# 4_analog_circuits.net
KiCad netlist of a schematic drawn in Altium Designer
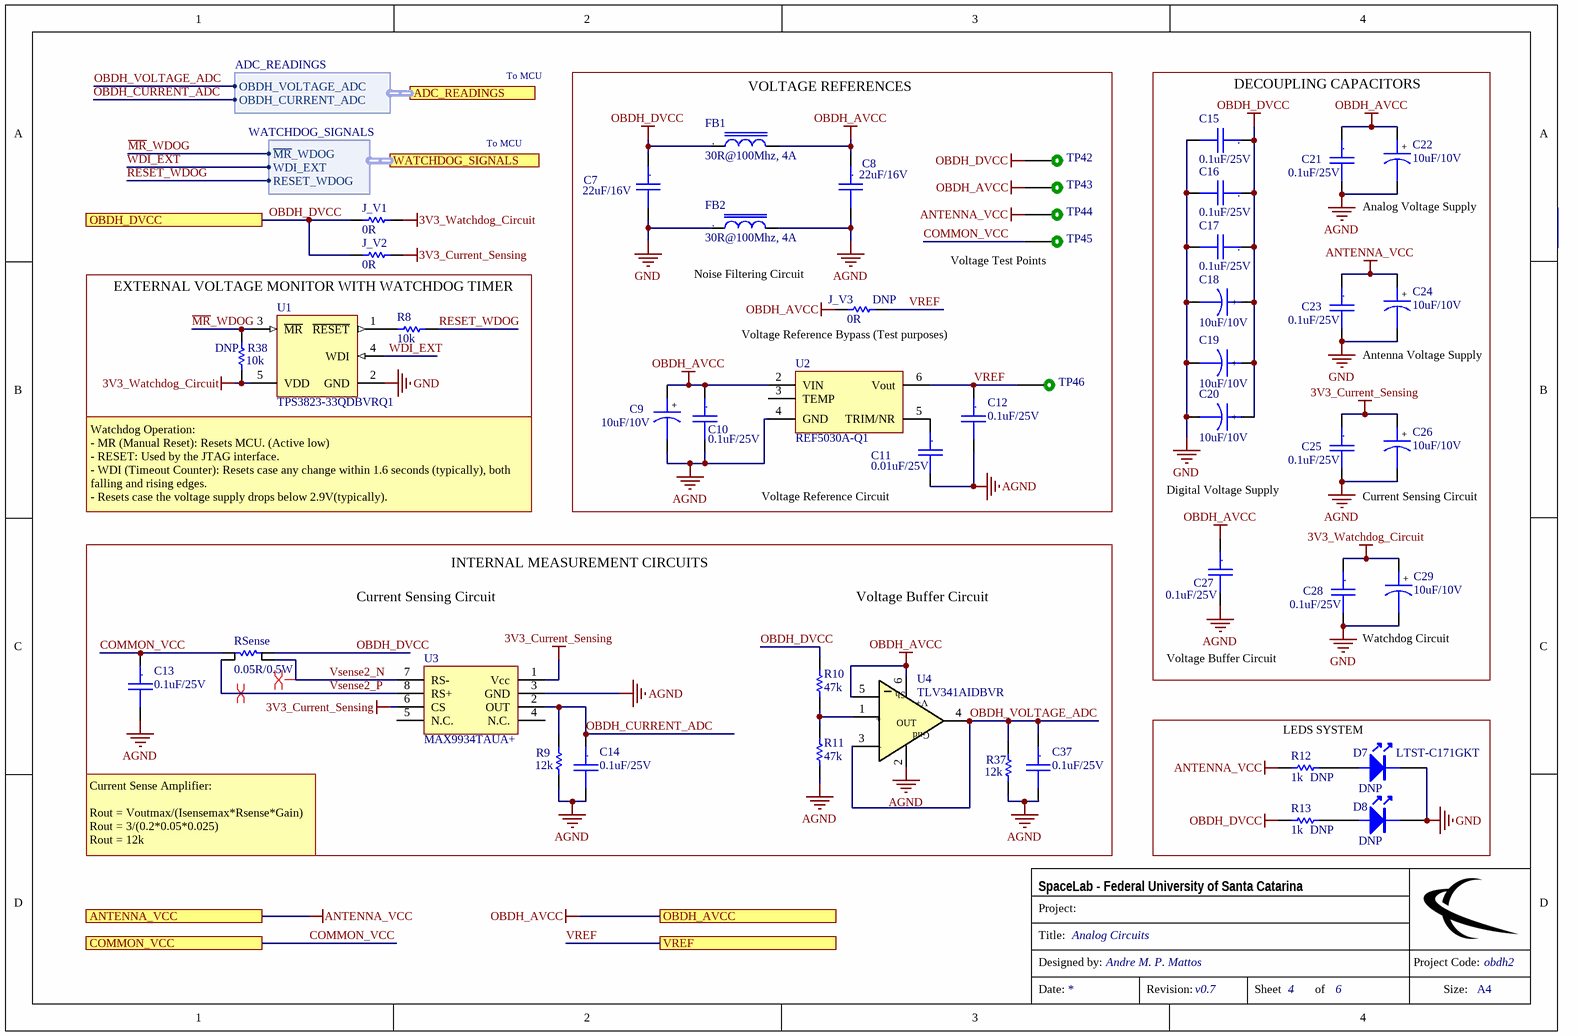
[diagram p0: 4_analog_circuits.schdoc]

(export (version "E")
  (design (tool "Eeschema 10.0.6"))
  (components
    (comp (ref "C7")
      (value "22uF/16V")
      (footprint "CC1210")
      (description "CAP CER 22uF 16V 10% X7R 1210")
      (fields (field (name "PARTNUMBER") "C3225X7R1C226K250AC"))
      (libsource (lib "OBDH_Eng_Model_2_ALT") (part "Cap_Cer_X7R_0.01uF_16V_1210"))
    )
    (comp (ref "C8")
      (value "22uF/16V")
      (footprint "CC1210")
      (description "CAP CER 22uF 16V 10% X7R 1210")
      (fields (field (name "PARTNUMBER") "C3225X7R1C226K250AC"))
      (libsource (lib "OBDH_Eng_Model_2_ALT") (part "Cap_Cer_X7R_0.01uF_16V_1210"))
    )
    (comp (ref "C9")
      (value "10uF/10V")
      (footprint "CC0805_Tantalum")
      (description "CAP Tantalum 10uF 6.3V 10% 0805")
      (fields (field (name "PARTNUMBER") "TPSR106K006R1000"))
      (libsource (lib "") (part "Cap_Tant_SMD_10uF_6V3_0805_1"))
    )
    (comp (ref "C10")
      (value "0.1uF/25V")
      (footprint "CC0805")
      (description "CAP CER 0.1UF 25V 10% X7R 0805")
      (fields (field (name "PARTNUMBER") "CC0805KRX7R8BB104"))
      (libsource (lib "OBDH_Eng_Model_2_ALT") (part "Cap_Cer_X7R_0.1uF_25V_0805"))
    )
    (comp (ref "C11")
      (value "0.01uF/25V")
      (footprint "CC0805")
      (description "CAP CER 0.01uF 25V 10% X7R 0805")
      (fields (field (name "PARTNUMBER") "CL21B103KAANNNC"))
      (libsource (lib "OBDH_Eng_Model_2_ALT") (part "Cap_Cer_X7R_0.01uF_50V_0805"))
    )
    (comp (ref "C12")
      (value "0.1uF/25V")
      (footprint "CC0805")
      (description "CAP CER 0.1UF 25V 10% X7R 0805")
      (fields (field (name "PARTNUMBER") "CC0805KRX7R8BB104"))
      (libsource (lib "OBDH_Eng_Model_2_ALT") (part "Cap_Cer_X7R_0.1uF_25V_0805"))
    )
    (comp (ref "C13")
      (value "0.1uF/25V")
      (footprint "CC0805")
      (description "CAP CER 0.1UF 25V 10% X7R 0805")
      (fields (field (name "PARTNUMBER") "CC0805KRX7R8BB104"))
      (libsource (lib "OBDH_Eng_Model_2_ALT") (part "Cap_Cer_X7R_0.1uF_25V_0805"))
    )
    (comp (ref "C14")
      (value "0.1uF/25V")
      (footprint "CC0805")
      (description "CAP CER 0.1UF 25V 10% X7R 0805")
      (fields (field (name "PARTNUMBER") "CC0805KRX7R8BB104"))
      (libsource (lib "OBDH_Eng_Model_2_ALT") (part "Cap_Cer_X7R_0.1uF_25V_0805"))
    )
    (comp (ref "C15")
      (value "0.1uF/25V")
      (footprint "CC0805")
      (description "CAP CER 0.1UF 25V 10% X7R 0805")
      (fields (field (name "PARTNUMBER") "CC0805KRX7R8BB104"))
      (libsource (lib "OBDH_Eng_Model_2_ALT") (part "Cap_Cer_X7R_0.1uF_25V_0805"))
    )
    (comp (ref "C16")
      (value "0.1uF/25V")
      (footprint "CC0805")
      (description "CAP CER 0.1UF 25V 10% X7R 0805")
      (fields (field (name "PARTNUMBER") "CC0805KRX7R8BB104"))
      (libsource (lib "OBDH_Eng_Model_2_ALT") (part "Cap_Cer_X7R_0.1uF_25V_0805"))
    )
    (comp (ref "C17")
      (value "0.1uF/25V")
      (footprint "CC0805")
      (description "CAP CER 0.1UF 25V 10% X7R 0805")
      (fields (field (name "PARTNUMBER") "CC0805KRX7R8BB104"))
      (libsource (lib "OBDH_Eng_Model_2_ALT") (part "Cap_Cer_X7R_0.1uF_25V_0805"))
    )
    (comp (ref "C18")
      (value "10uF/10V")
      (footprint "CC0805_Tantalum")
      (description "CAP Tantalum 10uF 6.3V 10% 0805")
      (fields (field (name "PARTNUMBER") "TPSR106K006R1000"))
      (libsource (lib "OBDH_Eng_Model_2_ALT") (part "Cap_Tant_SMD_10uF_6V3_0805"))
    )
    (comp (ref "C19")
      (value "10uF/10V")
      (footprint "CC0805_Tantalum")
      (description "CAP Tantalum 10uF 6.3V 10% 0805")
      (fields (field (name "PARTNUMBER") "TPSR106K006R1000"))
      (libsource (lib "OBDH_Eng_Model_2_ALT") (part "Cap_Tant_SMD_10uF_6V3_0805"))
    )
    (comp (ref "C20")
      (value "10uF/10V")
      (footprint "CC0805_Tantalum")
      (description "CAP Tantalum 10uF 6.3V 10% 0805")
      (fields (field (name "PARTNUMBER") "TPSR106K006R1000"))
      (libsource (lib "OBDH_Eng_Model_2_ALT") (part "Cap_Tant_SMD_10uF_6V3_0805"))
    )
    (comp (ref "C21")
      (value "0.1uF/25V")
      (footprint "CC0805")
      (description "CAP CER 0.1UF 25V 10% X7R 0805")
      (fields (field (name "PARTNUMBER") "CC0805KRX7R8BB104"))
      (libsource (lib "OBDH_Eng_Model_2_ALT") (part "Cap_Cer_X7R_0.1uF_25V_0805"))
    )
    (comp (ref "C22")
      (value "10uF/10V")
      (footprint "CC0805_Tantalum")
      (description "CAP Tantalum 10uF 10V 20% 0805")
      (fields (field (name "PARTNUMBER") "TPSP106M010R2000"))
      (libsource (lib "OBDH_Eng_Model_2_ALT") (part "Cap_Tant_SMD_10uF_10V_0805"))
    )
    (comp (ref "C23")
      (value "0.1uF/25V")
      (footprint "CC0805")
      (description "CAP CER 0.1UF 25V 10% X7R 0805")
      (fields (field (name "PARTNUMBER") "CC0805KRX7R8BB104"))
      (libsource (lib "OBDH_Eng_Model_2_ALT") (part "Cap_Cer_X7R_0.1uF_25V_0805"))
    )
    (comp (ref "C24")
      (value "10uF/10V")
      (footprint "CC0805_Tantalum")
      (description "CAP Tantalum 10uF 10V 20% 0805")
      (fields (field (name "PARTNUMBER") "TPSP106M010R2000"))
      (libsource (lib "OBDH_Eng_Model_2_ALT") (part "Cap_Tant_SMD_10uF_10V_0805"))
    )
    (comp (ref "C25")
      (value "0.1uF/25V")
      (footprint "CC0805")
      (description "CAP CER 0.1UF 25V 10% X7R 0805")
      (fields (field (name "PARTNUMBER") "CC0805KRX7R8BB104"))
      (libsource (lib "OBDH_Eng_Model_2_ALT") (part "Cap_Cer_X7R_0.1uF_25V_0805"))
    )
    (comp (ref "C26")
      (value "10uF/10V")
      (footprint "CC0805_Tantalum")
      (description "CAP Tantalum 10uF 10V 20% 0805")
      (fields (field (name "PARTNUMBER") "TPSP106M010R2000"))
      (libsource (lib "OBDH_Eng_Model_2_ALT") (part "Cap_Tant_SMD_10uF_10V_0805"))
    )
    (comp (ref "C27")
      (value "0.1uF/25V")
      (footprint "CC0805")
      (description "CAP CER 0.1UF 25V 10% X7R 0805")
      (fields (field (name "PARTNUMBER") "CC0805KRX7R8BB104"))
      (libsource (lib "FloripaSatSchlib") (part "Cap_Cer_X7R_0.1uF_25V_0805"))
    )
    (comp (ref "C28")
      (value "0.1uF/25V")
      (footprint "CC0805")
      (description "CAP CER 0.1UF 25V 10% X7R 0805")
      (fields (field (name "PARTNUMBER") "CC0805KRX7R8BB104"))
      (libsource (lib "OBDH_Eng_Model_2_ALT") (part "Cap_Cer_X7R_0.1uF_25V_0805"))
    )
    (comp (ref "C29")
      (value "10uF/10V")
      (footprint "CC0805_Tantalum")
      (description "CAP Tantalum 10uF 10V 20% 0805")
      (fields (field (name "PARTNUMBER") "TPSP106M010R2000"))
      (libsource (lib "OBDH_Eng_Model_2_ALT") (part "Cap_Tant_SMD_10uF_10V_0805"))
    )
    (comp (ref "C37")
      (value "0.1uF/25V")
      (footprint "CC0805")
      (description "CAP CER 0.1UF 25V 10% X7R 0805")
      (fields (field (name "PARTNUMBER") "CC0805KRX7R8BB104"))
      (libsource (lib "OBDH_Eng_Model_2_ALT") (part "Cap_Cer_X7R_0.1uF_25V_0805"))
    )
    (comp (ref "D7")
      (value "DNP")
      (footprint "0805-LED")
      (description "SMD Green LED")
      (fields (field (name "PARTNUMBER") "LTST-C171GKT"))
      (libsource (lib "OBDH_Eng_Model_2_ALT") (part "LED/G_0805"))
    )
    (comp (ref "D8")
      (value "DNP")
      (footprint "0805-LED")
      (description "SMD Green LED")
      (fields (field (name "PARTNUMBER") "LTST-C171GKT"))
      (libsource (lib "OBDH_Eng_Model_2_ALT") (part "LED/G_0805"))
    )
    (comp (ref "FB1")
      (value "30R@100Mhz, 4A")
      (footprint "IND0805")
      (description "Ferrite Bead 30 OHM 4A 100MHz")
      (fields (field (name "PARTNUMBER") "BLM21PG300SN1D"))
      (libsource (lib "schematics_library_legacy") (part "FB_30R_4A_100MHz_0805"))
    )
    (comp (ref "FB2")
      (value "30R@100Mhz, 4A")
      (footprint "IND0805")
      (description "Ferrite Bead 30 OHM 4A 100MHz")
      (fields (field (name "PARTNUMBER") "BLM21PG300SN1D"))
      (libsource (lib "schematics_library_legacy") (part "FB_30R_4A_100MHz_0805"))
    )
    (comp (ref "J_V1")
      (value "0R")
      (footprint "0805")
      (description "RES 0R OHM 1/8W JUMPER 0805")
      (fields (field (name "PARTNUMBER") "CRCW08050000Z0EA"))
      (libsource (lib "schematics_library_legacy") (part "R0R_JUMPER_1/8W_0805"))
    )
    (comp (ref "J_V2")
      (value "0R")
      (footprint "0805")
      (description "RES 0R OHM 1/8W JUMPER 0805")
      (fields (field (name "PARTNUMBER") "CRCW08050000Z0EA"))
      (libsource (lib "schematics_library_legacy") (part "R0R_JUMPER_1/8W_0805"))
    )
    (comp (ref "J_V3")
      (value "0R")
      (footprint "0805")
      (description "RES 0R OHM 1/8W JUMPER 0805")
      (fields (field (name "PARTNUMBER") "CRCW08050000Z0EA"))
      (libsource (lib "schematics_library_legacy") (part "R0R_JUMPER_1/8W_0805"))
    )
    (comp (ref "R8")
      (value "10k")
      (footprint "0805")
      (description "RES 10K OHM 1/8W 1%  0805")
      (fields (field (name "PARTNUMBER") "CRCW080510K0FKEA"))
      (libsource (lib "OBDH_Eng_Model_2_ALT") (part "R10k_1%_1/8W_0805"))
    )
    (comp (ref "R9")
      (value "12k")
      (footprint "0805")
      (description "RES 12K OHM 1/8W 1%  0805")
      (fields (field (name "PARTNUMBER") "RC0805FR-0712KL"))
      (libsource (lib "schematics_library_legacy") (part "R12k_1%_1/8W_0805"))
    )
    (comp (ref "R10")
      (value "47k")
      (footprint "0805")
      (description "RES 47k OHM 1/8W 1% 0805")
      (fields (field (name "PARTNUMBER") "RC0805FR-0747KL"))
      (libsource (lib "schematics_library_legacy") (part "R47k_1%_1/8W_0805"))
    )
    (comp (ref "R11")
      (value "47k")
      (footprint "0805")
      (description "RES 47k OHM 1/8W 1% 0805")
      (fields (field (name "PARTNUMBER") "RC0805FR-0747KL"))
      (libsource (lib "schematics_library_legacy") (part "R47k_1%_1/8W_0805"))
    )
    (comp (ref "R12")
      (value "1k")
      (footprint "0805")
      (description "RES 1.0K OHM 1/8W 1% 0805")
      (fields (field (name "PARTNUMBER") "RC0805FR-071KL"))
      (libsource (lib "OBDH_Eng_Model_2_ALT") (part "R1.0k_1%_1/8W_0805"))
    )
    (comp (ref "R13")
      (value "1k")
      (footprint "0805")
      (description "RES 1.0K OHM 1/8W 1% 0805")
      (fields (field (name "PARTNUMBER") "RC0805FR-071KL"))
      (libsource (lib "OBDH_Eng_Model_2_ALT") (part "R1.0k_1%_1/8W_0805"))
    )
    (comp (ref "R37")
      (value "12k")
      (footprint "0805")
      (description "RES 12K OHM 1/8W 1%  0805")
      (fields (field (name "PARTNUMBER") "RC0805FR-0712KL"))
      (libsource (lib "schematics_library_legacy") (part "R12k_1%_1/8W_0805"))
    )
    (comp (ref "R38")
      (value "10k")
      (footprint "0805")
      (description "RES 10K OHM 1/8W 1%  0805")
      (fields (field (name "PARTNUMBER") "CRCW080510K0FKEA"))
      (libsource (lib "OBDH_Eng_Model_2_ALT") (part "R10k_1%_1/8W_0805"))
    )
    (comp (ref "RSense")
      (value "0.05R/0.5W")
      (footprint "1206 - ohmite")
      (description "Current Sense Resistors - SMD 0.05ohm .5% 4 Terminal")
      (fields (field (name "PARTNUMBER") "LVK12R050DER"))
      (libsource (lib "OBDH_Eng_Model_2_ALT") (part "R0.05R_0.5%_0.5W_1206"))
    )
    (comp (ref "TP42")
      (value "TEST_POINT_2")
      (footprint "TEST_POINT_2")
      (description "Test point")
      (libsource (lib "OBDH_Eng_Model_2_ALT") (part "TEST_POINT_2"))
    )
    (comp (ref "TP43")
      (value "TEST_POINT_2")
      (footprint "TEST_POINT_2")
      (description "Test point")
      (libsource (lib "OBDH_Eng_Model_2_ALT") (part "TEST_POINT_2"))
    )
    (comp (ref "TP44")
      (value "TEST_POINT_2")
      (footprint "TEST_POINT_2")
      (description "Test point")
      (libsource (lib "OBDH_Eng_Model_2_ALT") (part "TEST_POINT_2"))
    )
    (comp (ref "TP45")
      (value "TEST_POINT_2")
      (footprint "TEST_POINT_2")
      (description "Test point")
      (libsource (lib "OBDH_Eng_Model_2_ALT") (part "TEST_POINT_2"))
    )
    (comp (ref "TP46")
      (value "TEST_POINT_2")
      (footprint "TEST_POINT_2")
      (description "Test point")
      (libsource (lib "OBDH_Eng_Model_2_ALT") (part "TEST_POINT_2"))
    )
    (comp (ref "U1")
      (value "TPS3823-33QDBVRQ1")
      (footprint "DBV0005A_N")
      (fields (field (name "MANUFACTURER") "Texas Instruments"))
      (libsource (lib "OBDH_Eng_Model_2_ALT") (part "CMP-0338-00011-2"))
    )
    (comp (ref "U2")
      (value "REF5030A-Q1")
      (footprint "SOIC-8")
      (libsource (lib "OBDH_Eng_Model_2_ALT") (part "REF5030A-Q1"))
    )
    (comp (ref "U3")
      (value "MAX9934TAUA+")
      (footprint "MSOP-8")
      (libsource (lib "OBDH_Eng_Model_2_ALT") (part "MAX9934TAUA+"))
    )
    (comp (ref "U4")
      (value "TLV341AIDBVR")
      (footprint "SOT-23 6L")
      (libsource (lib "OBDH_Eng_Model_2_ALT") (part "TLV341AIDBVR"))
    )
  )
  (nets
    (net (code "3") (name "/COMMON_VCC") (class "Default")
      (node (ref "C13") (pin "1") (pinfunction "1_1") (pintype "passive"))
      (node (ref "RSense") (pin "1") (pinfunction "1_1") (pintype "passive"))
      (node (ref "TP45") (pin "1") (pinfunction "1_1") (pintype "passive"))
    )
    (net (code "4") (name "/OBDH_CURRENT_ADC") (class "Default")
      (node (ref "C14") (pin "1") (pinfunction "1_1") (pintype "passive"))
      (node (ref "R9") (pin "2") (pinfunction "2_2") (pintype "passive"))
      (node (ref "U3") (pin "2") (pinfunction "OUT_2") (pintype "passive"))
    )
    (net (code "5") (name "/OBDH_VOLTAGE_ADC") (class "Default")
      (node (ref "C37") (pin "1") (pinfunction "1_1") (pintype "passive"))
      (node (ref "R37") (pin "2") (pinfunction "2_2") (pintype "passive"))
      (node (ref "U4") (pin "3") (pinfunction "-IN_3") (pintype "passive"))
      (node (ref "U4") (pin "4") (pinfunction "OUT_4") (pintype "passive"))
    )
    (net (code "6") (name "/RESET_WDOG") (class "Default")
      (node (ref "R8") (pin "2") (pinfunction "2_2") (pintype "passive"))
    )
    (net (code "7") (name "/VREF") (class "Default")
      (node (ref "C12") (pin "1") (pinfunction "1_1") (pintype "passive"))
      (node (ref "J_V3") (pin "1") (pinfunction "1_1") (pintype "passive"))
      (node (ref "TP46") (pin "1") (pinfunction "1_1") (pintype "passive"))
      (node (ref "U2") (pin "6") (pinfunction "Vout_6") (pintype "passive"))
    )
    (net (code "8") (name "/Vsense2_N") (class "Default")
      (node (ref "RSense") (pin "4") (pinfunction "4_4") (pintype "passive"))
      (node (ref "U3") (pin "7") (pinfunction "RS-_7") (pintype "passive"))
    )
    (net (code "9") (name "/Vsense2_P") (class "Default")
      (node (ref "RSense") (pin "3") (pinfunction "3_3") (pintype "passive"))
      (node (ref "U3") (pin "8") (pinfunction "RS+_8") (pintype "passive"))
    )
    (net (code "10") (name "/WDI_EXT") (class "Default")
      (node (ref "U1") (pin "4") (pinfunction "WDI_4") (pintype "input"))
    )
    (net (code "13") (name "/~{MR}_WDOG") (class "Default")
      (node (ref "R38") (pin "2") (pinfunction "2_2") (pintype "passive"))
      (node (ref "U1") (pin "3") (pinfunction "~{MR}_3") (pintype "input"))
    )
    (net (code "14") (name "3V3_Current_Sensing") (class "Default")
      (node (ref "C25") (pin "1") (pinfunction "1_1") (pintype "passive"))
      (node (ref "C26") (pin "1") (pinfunction "1_1") (pintype "passive"))
      (node (ref "J_V2") (pin "1") (pinfunction "1_1") (pintype "passive"))
      (node (ref "U3") (pin "1") (pinfunction "Vcc_1") (pintype "passive"))
      (node (ref "U3") (pin "6") (pinfunction "CS_6") (pintype "passive"))
    )
    (net (code "15") (name "3V3_Watchdog_Circuit") (class "Default")
      (node (ref "C28") (pin "1") (pinfunction "1_1") (pintype "passive"))
      (node (ref "C29") (pin "1") (pinfunction "1_1") (pintype "passive"))
      (node (ref "J_V1") (pin "1") (pinfunction "1_1") (pintype "passive"))
      (node (ref "R38") (pin "1") (pinfunction "1_1") (pintype "passive"))
      (node (ref "U1") (pin "5") (pinfunction "VDD_5") (pintype "power_in"))
    )
    (net (code "16") (name "AGND") (class "Default")
      (node (ref "C10") (pin "2") (pinfunction "2_2") (pintype "passive"))
      (node (ref "C11") (pin "2") (pinfunction "2_2") (pintype "passive"))
      (node (ref "C12") (pin "2") (pinfunction "2_2") (pintype "passive"))
      (node (ref "C13") (pin "2") (pinfunction "2_2") (pintype "passive"))
      (node (ref "C14") (pin "2") (pinfunction "2_2") (pintype "passive"))
      (node (ref "C21") (pin "2") (pinfunction "2_2") (pintype "passive"))
      (node (ref "C22") (pin "2") (pinfunction "2_2") (pintype "passive"))
      (node (ref "C25") (pin "2") (pinfunction "2_2") (pintype "passive"))
      (node (ref "C26") (pin "2") (pinfunction "2_2") (pintype "passive"))
      (node (ref "C27") (pin "2") (pinfunction "2_2") (pintype "passive"))
      (node (ref "C37") (pin "2") (pinfunction "2_2") (pintype "passive"))
      (node (ref "C8") (pin "2") (pinfunction "2_2") (pintype "passive"))
      (node (ref "C9") (pin "2") (pinfunction "2_2") (pintype "passive"))
      (node (ref "FB2") (pin "2") (pinfunction "2_2") (pintype "passive"))
      (node (ref "R11") (pin "1") (pinfunction "1_1") (pintype "passive"))
      (node (ref "R37") (pin "1") (pinfunction "1_1") (pintype "passive"))
      (node (ref "R9") (pin "1") (pinfunction "1_1") (pintype "passive"))
      (node (ref "U2") (pin "4") (pinfunction "GND_4") (pintype "passive"))
      (node (ref "U3") (pin "3") (pinfunction "GND_3") (pintype "passive"))
      (node (ref "U4") (pin "2") (pinfunction "Gnd_2") (pintype "passive"))
    )
    (net (code "17") (name "ANTENNA_VCC") (class "Default")
      (node (ref "C23") (pin "1") (pinfunction "1_1") (pintype "passive"))
      (node (ref "C24") (pin "1") (pinfunction "1_1") (pintype "passive"))
      (node (ref "R12") (pin "2") (pinfunction "2_2") (pintype "passive"))
      (node (ref "TP44") (pin "1") (pinfunction "1_1") (pintype "passive"))
    )
    (net (code "18") (name "GND") (class "Default")
      (node (ref "C15") (pin "2") (pinfunction "2_2") (pintype "passive"))
      (node (ref "C16") (pin "2") (pinfunction "2_2") (pintype "passive"))
      (node (ref "C17") (pin "2") (pinfunction "2_2") (pintype "passive"))
      (node (ref "C18") (pin "2") (pinfunction "2_2") (pintype "passive"))
      (node (ref "C19") (pin "2") (pinfunction "2_2") (pintype "passive"))
      (node (ref "C20") (pin "2") (pinfunction "2_2") (pintype "passive"))
      (node (ref "C23") (pin "2") (pinfunction "2_2") (pintype "passive"))
      (node (ref "C24") (pin "2") (pinfunction "2_2") (pintype "passive"))
      (node (ref "C28") (pin "2") (pinfunction "2_2") (pintype "passive"))
      (node (ref "C29") (pin "2") (pinfunction "2_2") (pintype "passive"))
      (node (ref "C7") (pin "2") (pinfunction "2_2") (pintype "passive"))
      (node (ref "D7") (pin "2") (pinfunction "K_2") (pintype "passive"))
      (node (ref "D8") (pin "2") (pinfunction "K_2") (pintype "passive"))
      (node (ref "FB2") (pin "1") (pinfunction "1_1") (pintype "passive"))
      (node (ref "U1") (pin "2") (pinfunction "GND_2") (pintype "power_in"))
    )
    (net (code "19") (name "Net-(D7-A)") (class "Default")
      (node (ref "D7") (pin "1") (pinfunction "A_1") (pintype "passive"))
      (node (ref "R12") (pin "1") (pinfunction "1_1") (pintype "passive"))
    )
    (net (code "20") (name "Net-(D8-A)") (class "Default")
      (node (ref "D8") (pin "1") (pinfunction "A_1") (pintype "passive"))
      (node (ref "R13") (pin "1") (pinfunction "1_1") (pintype "passive"))
    )
    (net (code "21") (name "Net-(U1-~{RESET})") (class "Default")
      (node (ref "R8") (pin "1") (pinfunction "1_1") (pintype "passive"))
      (node (ref "U1") (pin "1") (pinfunction "~{RESET}_1") (pintype "output"))
    )
    (net (code "22") (name "Net-(U2-TRIM{slash}NR)") (class "Default")
      (node (ref "C11") (pin "1") (pinfunction "1_1") (pintype "passive"))
      (node (ref "U2") (pin "5") (pinfunction "TRIM/NR_5") (pintype "passive"))
    )
    (net (code "23") (name "Net-(U4-+IN)") (class "Default")
      (node (ref "R10") (pin "1") (pinfunction "1_1") (pintype "passive"))
      (node (ref "R11") (pin "2") (pinfunction "2_2") (pintype "passive"))
      (node (ref "U4") (pin "1") (pinfunction "+IN_1") (pintype "passive"))
    )
    (net (code "24") (name "OBDH_AVCC") (class "Default")
      (node (ref "C10") (pin "1") (pinfunction "1_1") (pintype "passive"))
      (node (ref "C21") (pin "1") (pinfunction "1_1") (pintype "passive"))
      (node (ref "C22") (pin "1") (pinfunction "1_1") (pintype "passive"))
      (node (ref "C27") (pin "1") (pinfunction "1_1") (pintype "passive"))
      (node (ref "C8") (pin "1") (pinfunction "1_1") (pintype "passive"))
      (node (ref "C9") (pin "1") (pinfunction "1_1") (pintype "passive"))
      (node (ref "FB1") (pin "2") (pinfunction "2_2") (pintype "passive"))
      (node (ref "J_V3") (pin "2") (pinfunction "2_2") (pintype "passive"))
      (node (ref "TP43") (pin "1") (pinfunction "1_1") (pintype "passive"))
      (node (ref "U2") (pin "2") (pinfunction "VIN_2") (pintype "passive"))
      (node (ref "U4") (pin "5") (pinfunction "EN_5") (pintype "passive"))
      (node (ref "U4") (pin "6") (pinfunction "V+_6") (pintype "passive"))
    )
    (net (code "25") (name "OBDH_DVCC") (class "Default")
      (node (ref "C15") (pin "1") (pinfunction "1_1") (pintype "passive"))
      (node (ref "C16") (pin "1") (pinfunction "1_1") (pintype "passive"))
      (node (ref "C17") (pin "1") (pinfunction "1_1") (pintype "passive"))
      (node (ref "C18") (pin "1") (pinfunction "1_1") (pintype "passive"))
      (node (ref "C19") (pin "1") (pinfunction "1_1") (pintype "passive"))
      (node (ref "C20") (pin "1") (pinfunction "1_1") (pintype "passive"))
      (node (ref "C7") (pin "1") (pinfunction "1_1") (pintype "passive"))
      (node (ref "FB1") (pin "1") (pinfunction "1_1") (pintype "passive"))
      (node (ref "J_V1") (pin "2") (pinfunction "2_2") (pintype "passive"))
      (node (ref "J_V2") (pin "2") (pinfunction "2_2") (pintype "passive"))
      (node (ref "R10") (pin "2") (pinfunction "2_2") (pintype "passive"))
      (node (ref "R13") (pin "2") (pinfunction "2_2") (pintype "passive"))
      (node (ref "RSense") (pin "2") (pinfunction "2_2") (pintype "passive"))
      (node (ref "TP42") (pin "1") (pinfunction "1_1") (pintype "passive"))
    )
    (net (code "26") (name "unconnected-(U2-TEMP-Pad3)") (class "Default")
      (node (ref "U2") (pin "3") (pinfunction "TEMP_3") (pintype "passive"))
    )
    (net (code "27") (name "unconnected-(U3-N.C.-Pad4)") (class "Default")
      (node (ref "U3") (pin "4") (pinfunction "N.C._4") (pintype "passive"))
    )
    (net (code "28") (name "unconnected-(U3-N.C.-Pad5)") (class "Default")
      (node (ref "U3") (pin "5") (pinfunction "N.C._5") (pintype "passive"))
    )
  )
)
